# MPS.net
KiCad netlist of a schematic drawn in EAGLE
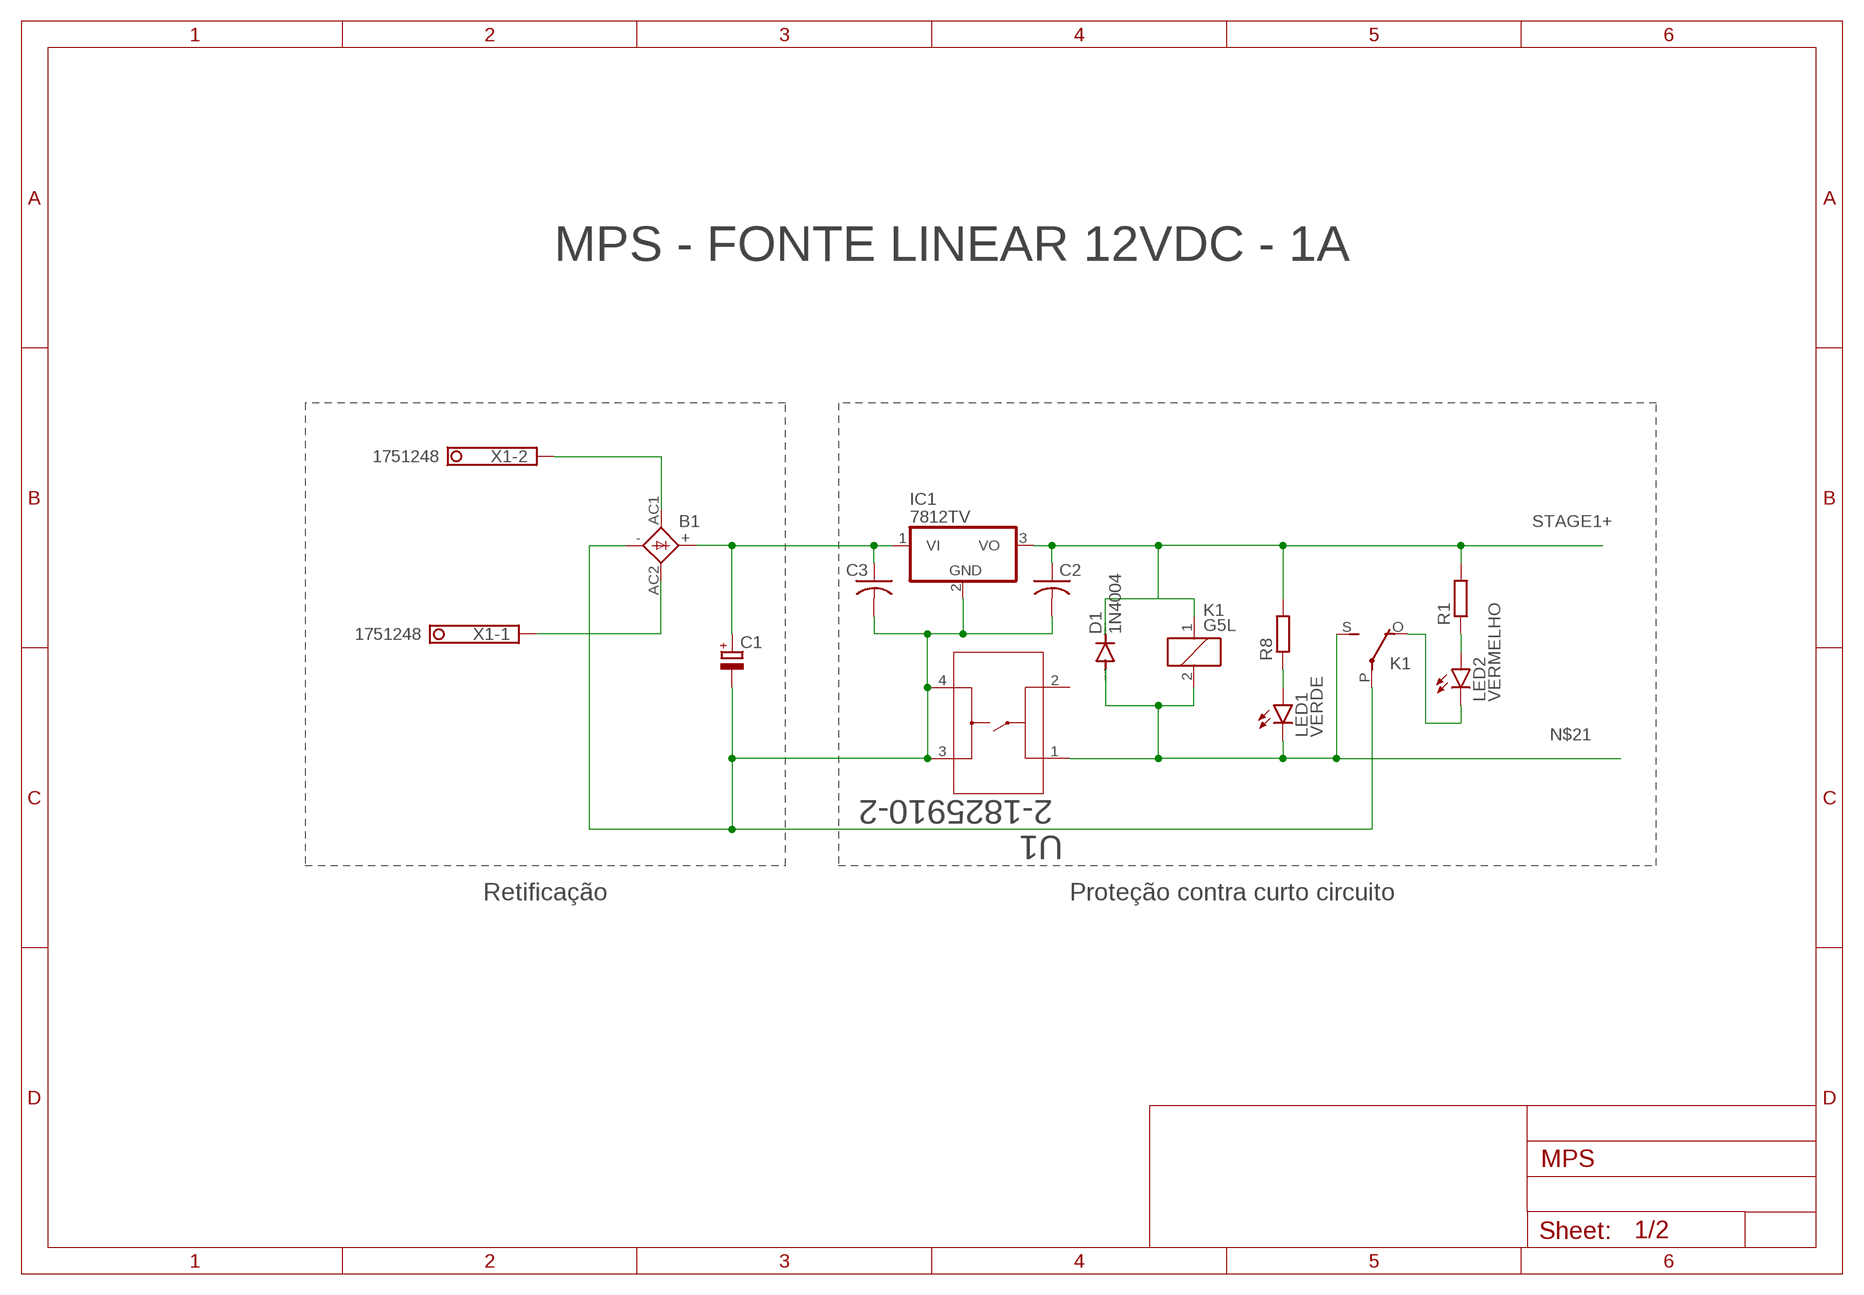
[diagram p0: schematic, sheet 1]
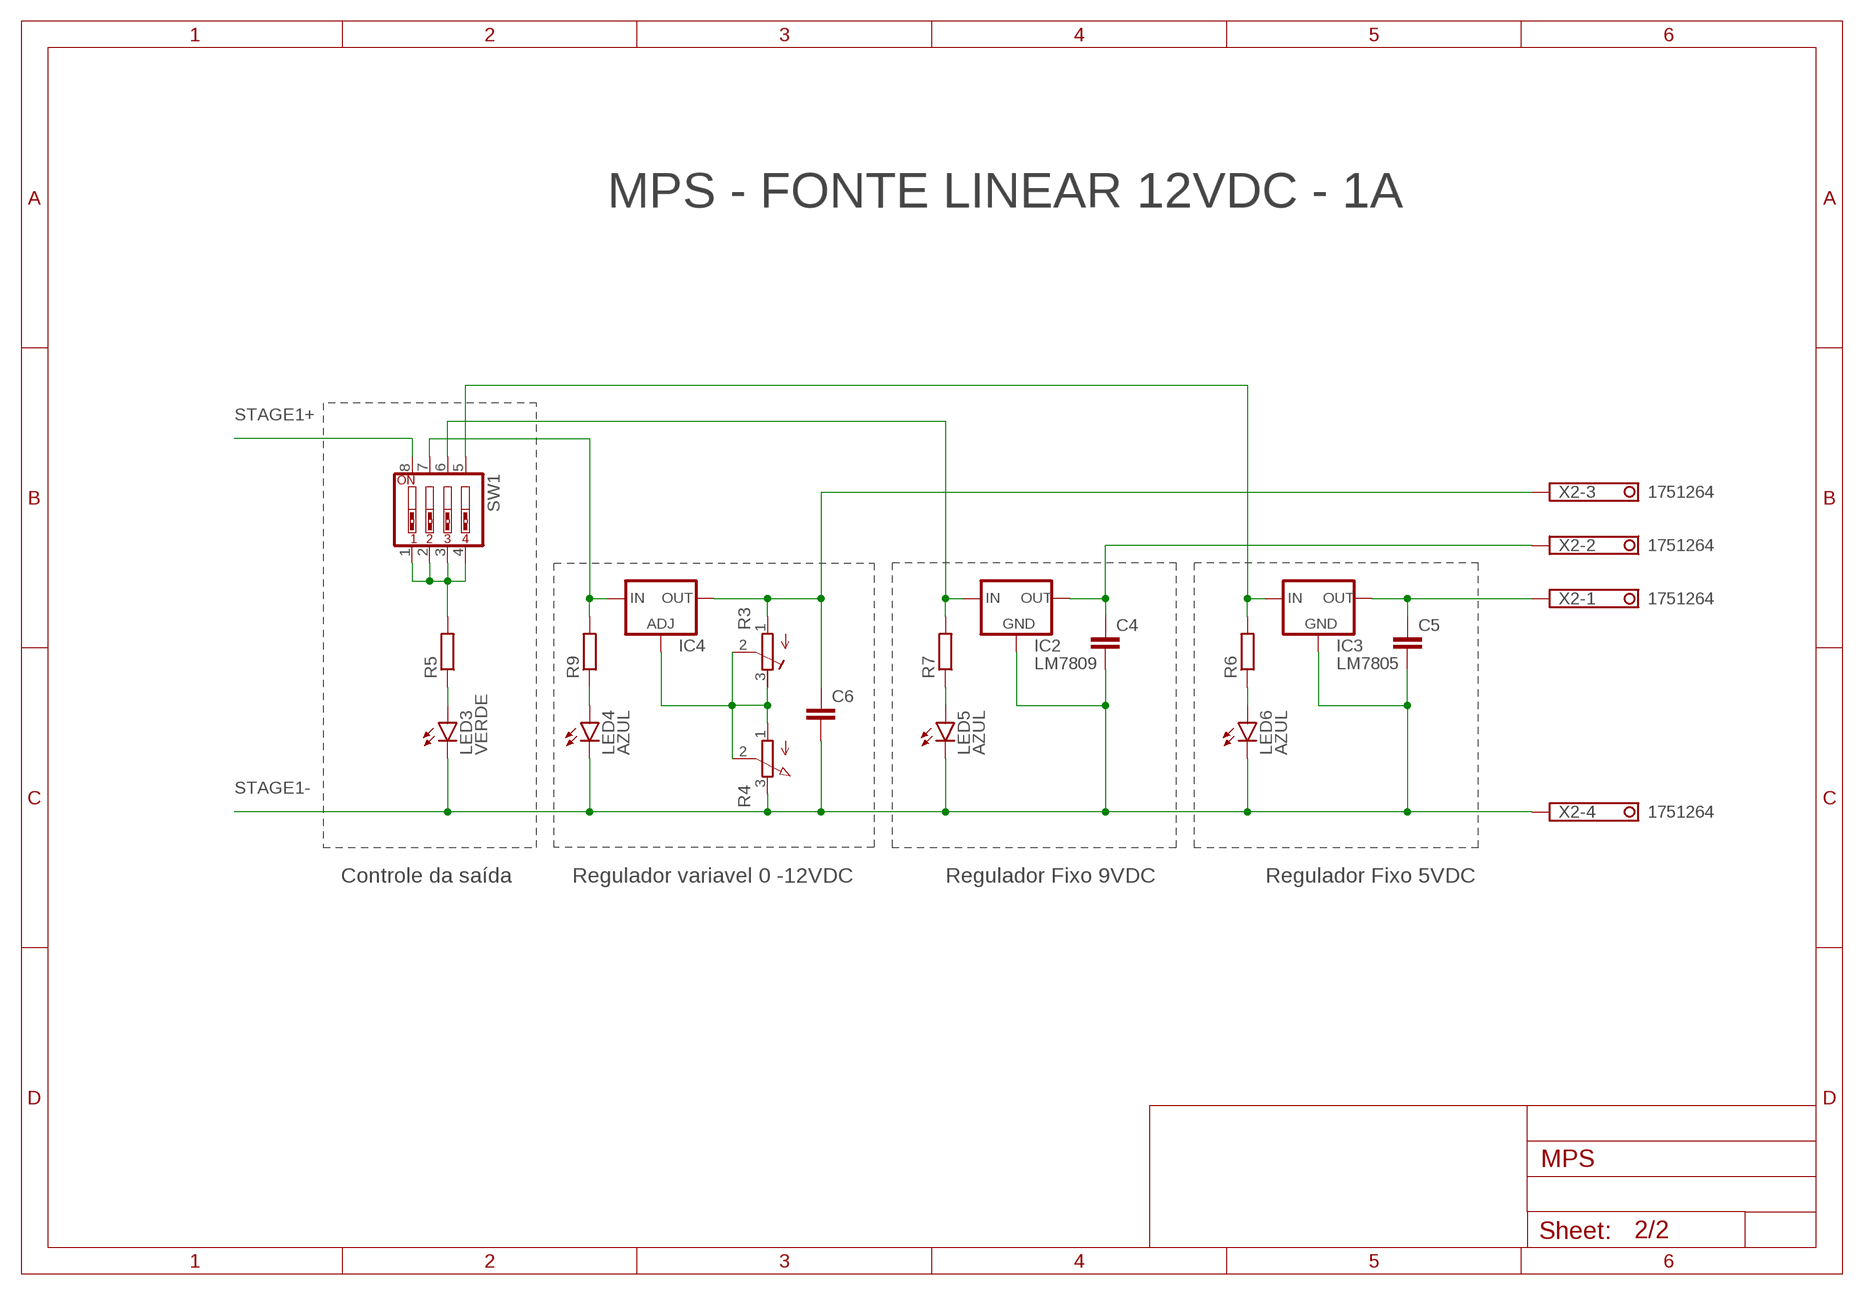
[diagram p1: schematic, sheet 2]

(export (version "E")
  (design (tool "Eeschema 10.0.6"))
  (components
    (comp (ref "B1")
      (value "2KBB-R")
      (footprint "eagle-import:2KBB-R")
      (libsource (lib "eagle-import") (part "2KBB-R"))
    )
    (comp (ref "C1")
      (value "CPOL-EUE2.5-7")
      (footprint "eagle-import:E2,5-7")
      (libsource (lib "eagle-import") (part "CPOL-EUE2.5-7"))
    )
    (comp (ref "C2")
      (value "C-US050-035X075")
      (footprint "eagle-import:C050-035X075")
      (libsource (lib "eagle-import") (part "C-US050-035X075"))
    )
    (comp (ref "C3")
      (value "C-US050-035X075")
      (footprint "eagle-import:C050-035X075")
      (libsource (lib "eagle-import") (part "C-US050-035X075"))
    )
    (comp (ref "D1")
      (value "1N4004")
      (footprint "eagle-import:DO41-10")
      (libsource (lib "eagle-import") (part "1N4004"))
    )
    (comp (ref "IC1")
      (value "7812TV")
      (footprint "eagle-import:TO220V")
      (libsource (lib "eagle-import") (part "78TV12"))
    )
    (comp (ref "K1")
      (value "G5L")
      (footprint "eagle-import:G5LE")
      (libsource (lib "eagle-import") (part "G5L"))
    )
    (comp (ref "LED1")
      (value "VERDE")
      (footprint "eagle-import:LED3MM")
      (libsource (lib "eagle-import") (part "LED3MM"))
    )
    (comp (ref "LED2")
      (value "VERMELHO")
      (footprint "eagle-import:LED3MM")
      (libsource (lib "eagle-import") (part "LED3MM"))
    )
    (comp (ref "R1")
      (value "R-EU_0207/7")
      (footprint "eagle-import:0207_7")
      (libsource (lib "eagle-import") (part "R-EU_0207/7"))
    )
    (comp (ref "R8")
      (value "R-EU_0207/7")
      (footprint "eagle-import:0207_7")
      (libsource (lib "eagle-import") (part "R-EU_0207/7"))
    )
    (comp (ref "U1")
      (value "2-1825910-2")
      (footprint "eagle-import:SWITCH_2-1825910-2")
      (fields (field (name "COPYRIGHT") "Copyright (C) 2016 Accelerated Designs. All rights reserved"))
      (libsource (lib "eagle-import") (part "2-1825910-2"))
    )
    (comp (ref "X1")
      (value "1751248")
      (footprint "eagle-import:1751248")
      (libsource (lib "eagle-import") (part "1751248"))
    )
    (comp (ref "C4")
      (value "C-EU025-030X050")
      (footprint "eagle-import:C025-030X050")
      (libsource (lib "eagle-import") (part "C-EU025-030X050"))
    )
    (comp (ref "C5")
      (value "C-EU025-030X050")
      (footprint "eagle-import:C025-030X050")
      (libsource (lib "eagle-import") (part "C-EU025-030X050"))
    )
    (comp (ref "C6")
      (value "C-EU025-030X050")
      (footprint "eagle-import:C025-030X050")
      (libsource (lib "eagle-import") (part "C-EU025-030X050"))
    )
    (comp (ref "IC2")
      (value "LM7809")
      (footprint "eagle-import:78XXS")
      (libsource (lib "eagle-import") (part "78XXS"))
    )
    (comp (ref "IC3")
      (value "LM7805")
      (footprint "eagle-import:78XXS")
      (libsource (lib "eagle-import") (part "78XXS"))
    )
    (comp (ref "IC4")
      (value "LM317TS")
      (footprint "eagle-import:317TS")
      (libsource (lib "eagle-import") (part "LM317TS"))
    )
    (comp (ref "LED3")
      (value "VERDE")
      (footprint "eagle-import:LED3MM")
      (libsource (lib "eagle-import") (part "LED3MM"))
    )
    (comp (ref "LED4")
      (value "AZUL")
      (footprint "eagle-import:LED3MM")
      (libsource (lib "eagle-import") (part "LED3MM"))
    )
    (comp (ref "LED5")
      (value "AZUL")
      (footprint "eagle-import:LED3MM")
      (libsource (lib "eagle-import") (part "LED3MM"))
    )
    (comp (ref "LED6")
      (value "AZUL")
      (footprint "eagle-import:LED3MM")
      (libsource (lib "eagle-import") (part "LED3MM"))
    )
    (comp (ref "R3")
      (value "R-TRIMM64W")
      (footprint "eagle-import:RTRIM64W")
      (libsource (lib "eagle-import") (part "R-TRIMM64W"))
    )
    (comp (ref "R4")
      (value "3RP/1610N")
      (footprint "eagle-import:3RP_1610N")
      (libsource (lib "eagle-import") (part "3RP/1610N"))
    )
    (comp (ref "R5")
      (value "R-EU_0207/7")
      (footprint "eagle-import:0207_7")
      (libsource (lib "eagle-import") (part "R-EU_0207/7"))
    )
    (comp (ref "R6")
      (value "R-EU_0207/7")
      (footprint "eagle-import:0207_7")
      (libsource (lib "eagle-import") (part "R-EU_0207/7"))
    )
    (comp (ref "R7")
      (value "R-EU_0207/7")
      (footprint "eagle-import:0207_7")
      (libsource (lib "eagle-import") (part "R-EU_0207/7"))
    )
    (comp (ref "R9")
      (value "R-EU_0207/7")
      (footprint "eagle-import:0207_7")
      (libsource (lib "eagle-import") (part "R-EU_0207/7"))
    )
    (comp (ref "SW1")
      (value "SW_DIP-4")
      (footprint "eagle-import:EDG-04")
      (libsource (lib "eagle-import") (part "SW_DIP-4"))
    )
    (comp (ref "X2")
      (value "1751264")
      (footprint "eagle-import:1751264")
      (libsource (lib "eagle-import") (part "1751264"))
    )
  )
  (nets
    (net (code "1") (name "N$21") (class "Default")
      (node (ref "D1") (pin "A") (pinfunction "A_A") (pintype "passive"))
      (node (ref "K1") (pin "2") (pinfunction "2_2") (pintype "passive"))
      (node (ref "K1") (pin "S") (pinfunction "S_S") (pintype "passive"))
      (node (ref "LED1") (pin "K") (pinfunction "C_K") (pintype "passive"))
      (node (ref "U1") (pin "1") (pinfunction "1_1") (pintype "passive"))
    )
    (net (code "2") (name "Net-(IC1-VI)") (class "Default")
      (node (ref "B1") (pin "+") (pinfunction "+_+") (pintype "passive"))
      (node (ref "C1") (pin "+") (pinfunction "+_+") (pintype "passive"))
      (node (ref "C3") (pin "1") (pinfunction "1_1") (pintype "passive"))
      (node (ref "IC1") (pin "1") (pinfunction "VI_1") (pintype "input"))
    )
    (net (code "3") (name "Net-(IC2-PadIN)") (class "Default")
      (node (ref "IC2") (pin "IN") (pinfunction "IN_IN") (pintype "input"))
      (node (ref "R7") (pin "2") (pinfunction "2_2") (pintype "passive"))
      (node (ref "SW1") (pin "6") (pinfunction "6_6") (pintype "passive"))
    )
    (net (code "4") (name "Net-(IC3-PadIN)") (class "Default")
      (node (ref "IC3") (pin "IN") (pinfunction "IN_IN") (pintype "input"))
      (node (ref "R6") (pin "2") (pinfunction "2_2") (pintype "passive"))
      (node (ref "SW1") (pin "5") (pinfunction "5_5") (pintype "passive"))
    )
    (net (code "5") (name "Net-(IC4-ADJ)") (class "Default")
      (node (ref "IC4") (pin "1") (pinfunction "ADJ_1") (pintype "input"))
      (node (ref "R3") (pin "2") (pinfunction "S_2") (pintype "passive"))
      (node (ref "R3") (pin "3") (pinfunction "E_3") (pintype "passive"))
      (node (ref "R4") (pin "1") (pinfunction "A_1") (pintype "passive"))
      (node (ref "R4") (pin "2") (pinfunction "S_2") (pintype "passive"))
    )
    (net (code "6") (name "Net-(IC4-IN)") (class "Default")
      (node (ref "IC4") (pin "3") (pinfunction "IN_3") (pintype "input"))
      (node (ref "R9") (pin "2") (pinfunction "2_2") (pintype "passive"))
      (node (ref "SW1") (pin "7") (pinfunction "7_7") (pintype "passive"))
    )
    (net (code "7") (name "Net-(IC4-OUT)") (class "Default")
      (node (ref "C6") (pin "1") (pinfunction "1_1") (pintype "passive"))
      (node (ref "IC4") (pin "2") (pinfunction "OUT_2") (pintype "passive"))
      (node (ref "R3") (pin "1") (pinfunction "A_1") (pintype "passive"))
      (node (ref "X2") (pin "3") (pinfunction "K_3") (pintype "passive"))
    )
    (net (code "8") (name "Net-(LED1-PadA)") (class "Default")
      (node (ref "LED1") (pin "A") (pinfunction "A_A") (pintype "passive"))
      (node (ref "R8") (pin "1") (pinfunction "1_1") (pintype "passive"))
    )
    (net (code "9") (name "Net-(LED2-C)") (class "Default")
      (node (ref "K1") (pin "O") (pinfunction "O_O") (pintype "passive"))
      (node (ref "LED2") (pin "K") (pinfunction "C_K") (pintype "passive"))
    )
    (net (code "10") (name "Net-(LED2-PadA)") (class "Default")
      (node (ref "LED2") (pin "A") (pinfunction "A_A") (pintype "passive"))
      (node (ref "R1") (pin "1") (pinfunction "1_1") (pintype "passive"))
    )
    (net (code "11") (name "Net-(LED3-PadA)") (class "Default")
      (node (ref "LED3") (pin "A") (pinfunction "A_A") (pintype "passive"))
      (node (ref "R5") (pin "1") (pinfunction "1_1") (pintype "passive"))
    )
    (net (code "12") (name "Net-(LED4-PadA)") (class "Default")
      (node (ref "LED4") (pin "A") (pinfunction "A_A") (pintype "passive"))
      (node (ref "R9") (pin "1") (pinfunction "1_1") (pintype "passive"))
    )
    (net (code "13") (name "Net-(LED5-PadA)") (class "Default")
      (node (ref "LED5") (pin "A") (pinfunction "A_A") (pintype "passive"))
      (node (ref "R7") (pin "1") (pinfunction "1_1") (pintype "passive"))
    )
    (net (code "14") (name "Net-(LED6-PadA)") (class "Default")
      (node (ref "LED6") (pin "A") (pinfunction "A_A") (pintype "passive"))
      (node (ref "R6") (pin "1") (pinfunction "1_1") (pintype "passive"))
    )
    (net (code "15") (name "Net-(R5-Pad2)") (class "Default")
      (node (ref "R5") (pin "2") (pinfunction "2_2") (pintype "passive"))
      (node (ref "SW1") (pin "1") (pinfunction "1_1") (pintype "passive"))
      (node (ref "SW1") (pin "2") (pinfunction "2_2") (pintype "passive"))
      (node (ref "SW1") (pin "3") (pinfunction "3_3") (pintype "passive"))
      (node (ref "SW1") (pin "4") (pinfunction "4_4") (pintype "passive"))
    )
    (net (code "16") (name "Net-(X1A-K)") (class "Default")
      (node (ref "B1") (pin "AC2") (pinfunction "AC2_AC2") (pintype "passive"))
      (node (ref "X1") (pin "1") (pinfunction "K_1") (pintype "passive"))
    )
    (net (code "17") (name "Net-(X1B-K)") (class "Default")
      (node (ref "B1") (pin "AC1") (pinfunction "AC1_AC1") (pintype "passive"))
      (node (ref "X1") (pin "2") (pinfunction "K_2") (pintype "passive"))
    )
    (net (code "18") (name "Net-(X2A-K)") (class "Default")
      (node (ref "C5") (pin "1") (pinfunction "1_1") (pintype "passive"))
      (node (ref "IC3") (pin "OUT") (pinfunction "OUT_OUT") (pintype "passive"))
      (node (ref "X2") (pin "1") (pinfunction "K_1") (pintype "passive"))
    )
    (net (code "19") (name "Net-(X2B-K)") (class "Default")
      (node (ref "C4") (pin "1") (pinfunction "1_1") (pintype "passive"))
      (node (ref "IC2") (pin "OUT") (pinfunction "OUT_OUT") (pintype "passive"))
      (node (ref "X2") (pin "2") (pinfunction "K_2") (pintype "passive"))
    )
    (net (code "20") (name "STAGE1+") (class "Default")
      (node (ref "C2") (pin "1") (pinfunction "1_1") (pintype "passive"))
      (node (ref "D1") (pin "C") (pinfunction "C_C") (pintype "passive"))
      (node (ref "IC1") (pin "3") (pinfunction "VO_3") (pintype "passive"))
      (node (ref "K1") (pin "1") (pinfunction "1_1") (pintype "passive"))
      (node (ref "R1") (pin "2") (pinfunction "2_2") (pintype "passive"))
      (node (ref "R8") (pin "2") (pinfunction "2_2") (pintype "passive"))
      (node (ref "SW1") (pin "8") (pinfunction "8_8") (pintype "passive"))
    )
    (net (code "21") (name "STAGE1-") (class "Default")
      (node (ref "B1") (pin "-") (pinfunction "-_-") (pintype "passive"))
      (node (ref "C1") (pin "-") (pinfunction "-_-") (pintype "passive"))
      (node (ref "C2") (pin "2") (pinfunction "2_2") (pintype "passive"))
      (node (ref "C3") (pin "2") (pinfunction "2_2") (pintype "passive"))
      (node (ref "C4") (pin "2") (pinfunction "2_2") (pintype "passive"))
      (node (ref "C5") (pin "2") (pinfunction "2_2") (pintype "passive"))
      (node (ref "C6") (pin "2") (pinfunction "2_2") (pintype "passive"))
      (node (ref "IC1") (pin "2") (pinfunction "GND_2") (pintype "passive"))
      (node (ref "IC2") (pin "GND") (pinfunction "GND_GND") (pintype "input"))
      (node (ref "IC3") (pin "GND") (pinfunction "GND_GND") (pintype "input"))
      (node (ref "K1") (pin "P") (pinfunction "P_P") (pintype "passive"))
      (node (ref "LED3") (pin "K") (pinfunction "C_K") (pintype "passive"))
      (node (ref "LED4") (pin "K") (pinfunction "C_K") (pintype "passive"))
      (node (ref "LED5") (pin "K") (pinfunction "C_K") (pintype "passive"))
      (node (ref "LED6") (pin "K") (pinfunction "C_K") (pintype "passive"))
      (node (ref "R4") (pin "3") (pinfunction "E_3") (pintype "passive"))
      (node (ref "U1") (pin "3") (pinfunction "3_3") (pintype "passive"))
      (node (ref "U1") (pin "4") (pinfunction "4_4") (pintype "passive"))
      (node (ref "X2") (pin "4") (pinfunction "K_4") (pintype "passive"))
    )
    (net (code "22") (name "unconnected-(U1-Pad2)") (class "Default")
      (node (ref "U1") (pin "2") (pinfunction "2_2") (pintype "passive"))
    )
  )
)
